# LegoConnector.net
KiCad netlist of a schematic drawn in EAGLE
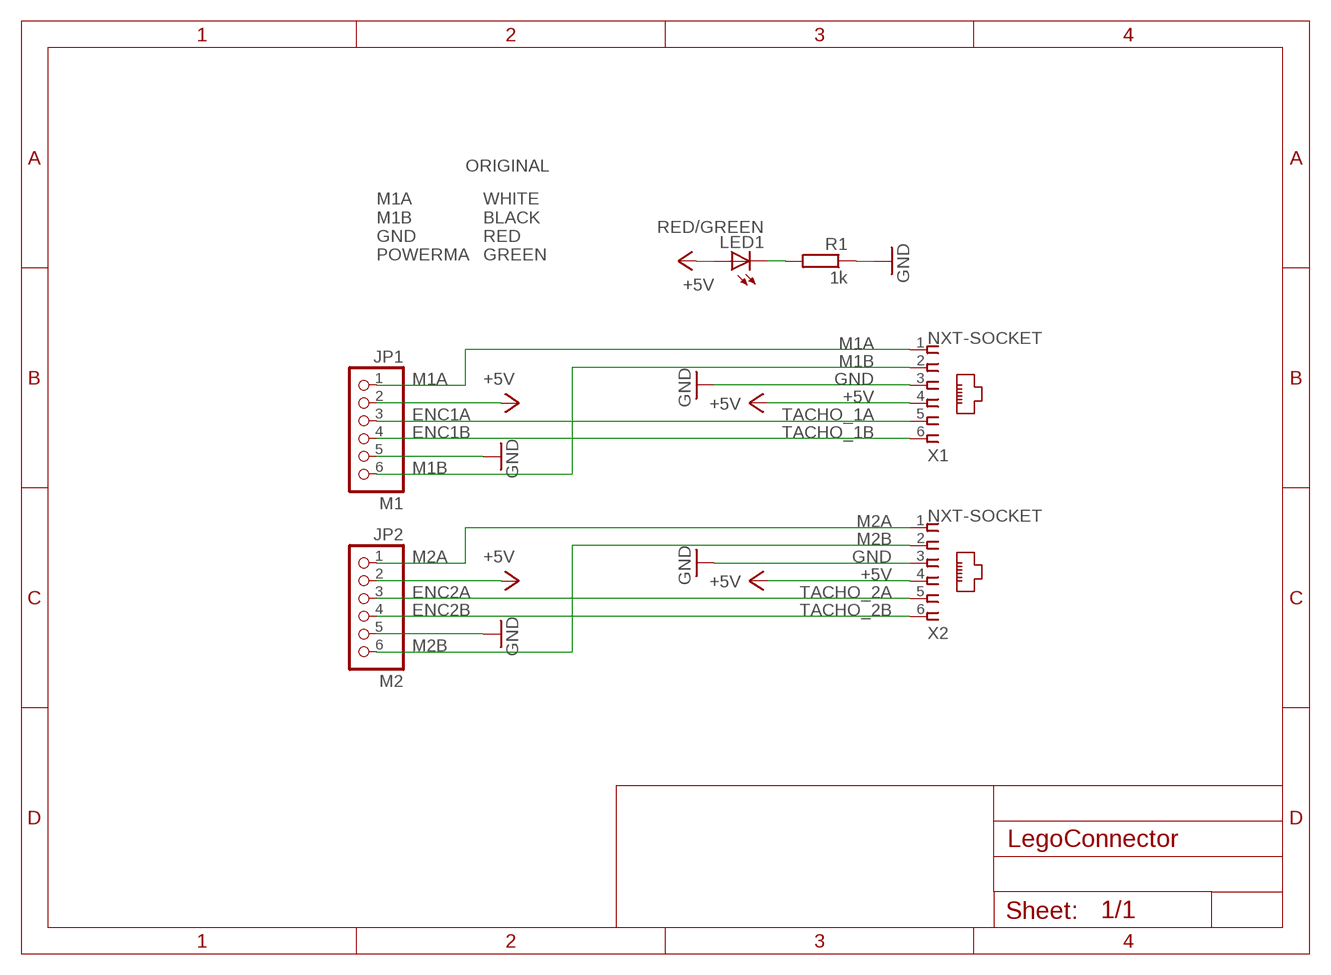
[diagram p0: schematic, sheet 1]

(export (version "E")
  (design (tool "Eeschema 10.0.6"))
  (components
    (comp (ref "JP1")
      (value "M1")
      (footprint "eagle-import:1X06")
      (libsource (lib "eagle-import") (part "PINHD-1X6"))
    )
    (comp (ref "JP2")
      (value "M2")
      (footprint "eagle-import:1X06")
      (libsource (lib "eagle-import") (part "PINHD-1X6"))
    )
    (comp (ref "LED1")
      (value "RED/GREEN")
      (footprint "eagle-import:SML0603")
      (libsource (lib "eagle-import") (part "LEDSML0603"))
    )
    (comp (ref "R1")
      (value "1k")
      (footprint "eagle-import:R0603")
      (libsource (lib "eagle-import") (part "R-EU_R0603"))
    )
    (comp (ref "X1")
      (value "NXT-SOCKET")
      (footprint "eagle-import:NXT-SOCKET")
      (libsource (lib "eagle-import") (part "NXT-SOCKET"))
    )
    (comp (ref "X2")
      (value "NXT-SOCKET")
      (footprint "eagle-import:NXT-SOCKET")
      (libsource (lib "eagle-import") (part "NXT-SOCKET"))
    )
  )
  (nets
    (net (code "1") (name "+5V") (class "Default")
      (node (ref "JP1") (pin "2") (pinfunction "2_2") (pintype "passive"))
      (node (ref "JP2") (pin "2") (pinfunction "2_2") (pintype "passive"))
      (node (ref "LED1") (pin "A") (pinfunction "A_A") (pintype "passive"))
      (node (ref "X1") (pin "4") (pinfunction "4_4") (pintype "passive"))
      (node (ref "X2") (pin "4") (pinfunction "4_4") (pintype "passive"))
    )
    (net (code "2") (name "/M1A") (class "Default")
      (node (ref "JP1") (pin "1") (pinfunction "1_1") (pintype "passive"))
      (node (ref "X1") (pin "1") (pinfunction "1_1") (pintype "passive"))
    )
    (net (code "3") (name "/M1B") (class "Default")
      (node (ref "JP1") (pin "6") (pinfunction "6_6") (pintype "passive"))
      (node (ref "X1") (pin "2") (pinfunction "2_2") (pintype "passive"))
    )
    (net (code "4") (name "/M2A") (class "Default")
      (node (ref "JP2") (pin "1") (pinfunction "1_1") (pintype "passive"))
      (node (ref "X2") (pin "1") (pinfunction "1_1") (pintype "passive"))
    )
    (net (code "5") (name "/M2B") (class "Default")
      (node (ref "JP2") (pin "6") (pinfunction "6_6") (pintype "passive"))
      (node (ref "X2") (pin "2") (pinfunction "2_2") (pintype "passive"))
    )
    (net (code "6") (name "/TACHO_1A") (class "Default")
      (node (ref "JP1") (pin "3") (pinfunction "3_3") (pintype "passive"))
      (node (ref "X1") (pin "5") (pinfunction "5_5") (pintype "passive"))
    )
    (net (code "7") (name "/TACHO_1B") (class "Default")
      (node (ref "JP1") (pin "4") (pinfunction "4_4") (pintype "passive"))
      (node (ref "X1") (pin "6") (pinfunction "6_6") (pintype "passive"))
    )
    (net (code "8") (name "/TACHO_2A") (class "Default")
      (node (ref "JP2") (pin "3") (pinfunction "3_3") (pintype "passive"))
      (node (ref "X2") (pin "5") (pinfunction "5_5") (pintype "passive"))
    )
    (net (code "9") (name "/TACHO_2B") (class "Default")
      (node (ref "JP2") (pin "4") (pinfunction "4_4") (pintype "passive"))
      (node (ref "X2") (pin "6") (pinfunction "6_6") (pintype "passive"))
    )
    (net (code "10") (name "GND") (class "Default")
      (node (ref "JP1") (pin "5") (pinfunction "5_5") (pintype "passive"))
      (node (ref "JP2") (pin "5") (pinfunction "5_5") (pintype "passive"))
      (node (ref "R1") (pin "1") (pinfunction "1_1") (pintype "passive"))
      (node (ref "X1") (pin "3") (pinfunction "3_3") (pintype "passive"))
      (node (ref "X2") (pin "3") (pinfunction "3_3") (pintype "passive"))
    )
    (net (code "11") (name "Net-(LED1-PadC)") (class "Default")
      (node (ref "LED1") (pin "C") (pinfunction "C_C") (pintype "passive"))
      (node (ref "R1") (pin "2") (pinfunction "2_2") (pintype "passive"))
    )
  )
)
